# IREncoder.net
KiCad netlist of a schematic drawn in EAGLE
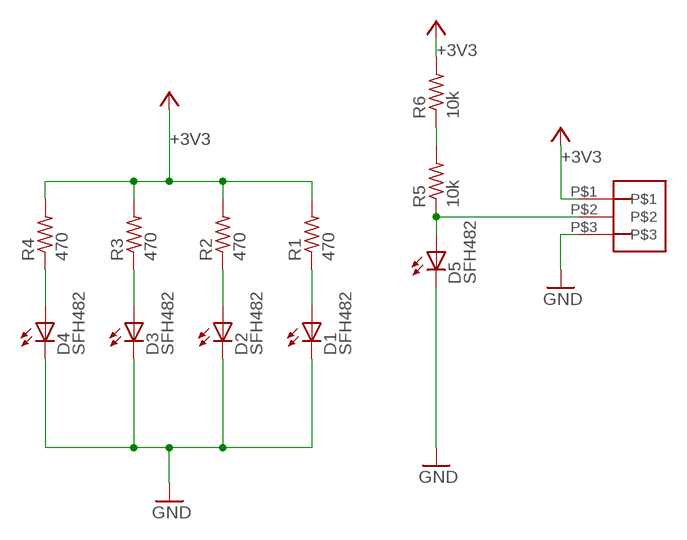
[diagram p0: schematic, sheet 1]

(export (version "E")
  (design (tool "Eeschema 10.0.6"))
  (components
    (comp (ref "D1")
      (value "SFH482")
      (footprint "eagle-import:SFH482")
      (libsource (lib "eagle-import") (part "SFH482"))
    )
    (comp (ref "D2")
      (value "SFH482")
      (footprint "eagle-import:SFH482")
      (libsource (lib "eagle-import") (part "SFH482"))
    )
    (comp (ref "D3")
      (value "SFH482")
      (footprint "eagle-import:SFH482")
      (libsource (lib "eagle-import") (part "SFH482"))
    )
    (comp (ref "D4")
      (value "SFH482")
      (footprint "eagle-import:SFH482")
      (libsource (lib "eagle-import") (part "SFH482"))
    )
    (comp (ref "D5")
      (value "SFH482")
      (footprint "eagle-import:SFH482")
      (libsource (lib "eagle-import") (part "SFH482"))
    )
    (comp (ref "J1")
      (value "3_PIN_JST-XH")
      (footprint "eagle-import:3_PIN_JST-XH")
      (libsource (lib "eagle-import") (part "3_PIN_JST-XH"))
    )
    (comp (ref "R1")
      (value "470")
      (footprint "eagle-import:R0805")
      (libsource (lib "eagle-import") (part "R-US_R0805"))
    )
    (comp (ref "R2")
      (value "470")
      (footprint "eagle-import:R0805")
      (libsource (lib "eagle-import") (part "R-US_R0805"))
    )
    (comp (ref "R3")
      (value "470")
      (footprint "eagle-import:R0805")
      (libsource (lib "eagle-import") (part "R-US_R0805"))
    )
    (comp (ref "R4")
      (value "470")
      (footprint "eagle-import:R0805")
      (libsource (lib "eagle-import") (part "R-US_R0805"))
    )
    (comp (ref "R5")
      (value "10k")
      (footprint "eagle-import:R0805")
      (libsource (lib "eagle-import") (part "R-US_R0805"))
    )
    (comp (ref "R6")
      (value "10k")
      (footprint "eagle-import:R0805")
      (libsource (lib "eagle-import") (part "R-US_R0805"))
    )
  )
  (nets
    (net (code "1") (name "+5V") (class "Default")
      (node (ref "J1") (pin "P$1") (pinfunction "P$1_P$1") (pintype "bidirectional"))
      (node (ref "R1") (pin "2") (pinfunction "2_2") (pintype "passive"))
      (node (ref "R2") (pin "2") (pinfunction "2_2") (pintype "passive"))
      (node (ref "R3") (pin "2") (pinfunction "2_2") (pintype "passive"))
      (node (ref "R4") (pin "2") (pinfunction "2_2") (pintype "passive"))
      (node (ref "R6") (pin "2") (pinfunction "2_2") (pintype "passive"))
    )
    (net (code "2") (name "GND") (class "Default")
      (node (ref "D1") (pin "K") (pinfunction "C_K") (pintype "passive"))
      (node (ref "D2") (pin "K") (pinfunction "C_K") (pintype "passive"))
      (node (ref "D3") (pin "K") (pinfunction "C_K") (pintype "passive"))
      (node (ref "D4") (pin "K") (pinfunction "C_K") (pintype "passive"))
      (node (ref "D5") (pin "K") (pinfunction "C_K") (pintype "passive"))
      (node (ref "J1") (pin "P$3") (pinfunction "P$3_P$3") (pintype "bidirectional"))
    )
    (net (code "3") (name "Net-(D1-PadA)") (class "Default")
      (node (ref "D1") (pin "A") (pinfunction "A_A") (pintype "passive"))
      (node (ref "R1") (pin "1") (pinfunction "1_1") (pintype "passive"))
    )
    (net (code "4") (name "Net-(D2-PadA)") (class "Default")
      (node (ref "D2") (pin "A") (pinfunction "A_A") (pintype "passive"))
      (node (ref "R2") (pin "1") (pinfunction "1_1") (pintype "passive"))
    )
    (net (code "5") (name "Net-(D3-PadA)") (class "Default")
      (node (ref "D3") (pin "A") (pinfunction "A_A") (pintype "passive"))
      (node (ref "R3") (pin "1") (pinfunction "1_1") (pintype "passive"))
    )
    (net (code "6") (name "Net-(D4-PadA)") (class "Default")
      (node (ref "D4") (pin "A") (pinfunction "A_A") (pintype "passive"))
      (node (ref "R4") (pin "1") (pinfunction "1_1") (pintype "passive"))
    )
    (net (code "7") (name "Net-(D5-PadA)") (class "Default")
      (node (ref "D5") (pin "A") (pinfunction "A_A") (pintype "passive"))
      (node (ref "J1") (pin "P$2") (pinfunction "P$2_P$2") (pintype "bidirectional"))
      (node (ref "R5") (pin "1") (pinfunction "1_1") (pintype "passive"))
    )
    (net (code "8") (name "Net-(R5-Pad2)") (class "Default")
      (node (ref "R5") (pin "2") (pinfunction "2_2") (pintype "passive"))
      (node (ref "R6") (pin "1") (pinfunction "1_1") (pintype "passive"))
    )
  )
)
